# VideoFiltering.net
KiCad netlist of a schematic drawn in Altium Designer
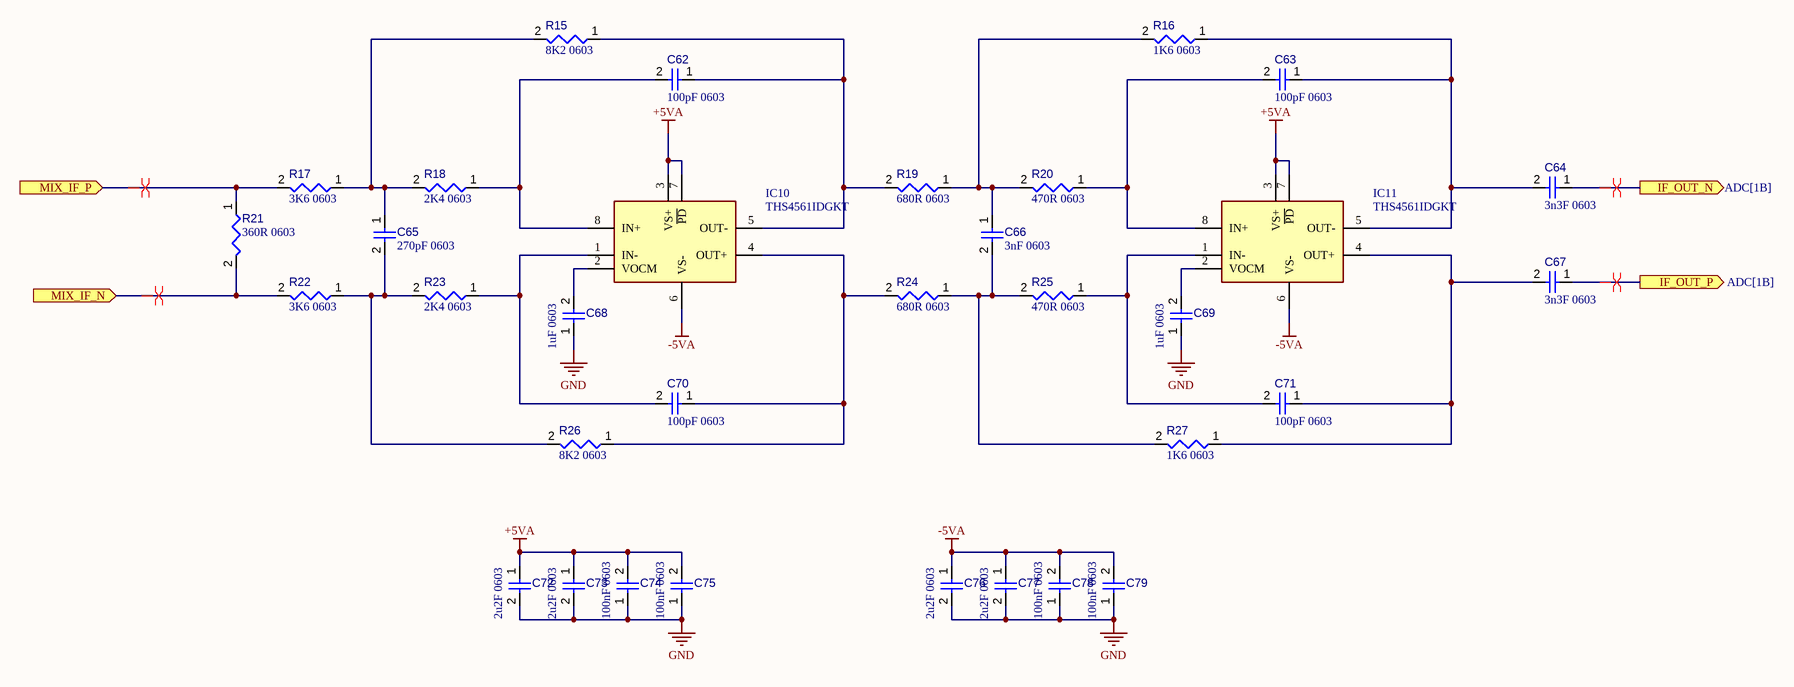
[diagram p0: VideoFiltering.SchDoc]

(export (version "E")
  (design (tool "Eeschema 10.0.6"))
  (components
    (comp (ref "C62")
      (value "100pF 0603")
      (footprint "CAPC0603(1608)100_L")
      (description "Chip Capacitor, 1µF +/-0.1%, 25V, 0603, Thickness 1 mm")
      (fields (field (name "TOLERANCE") "20%") (field (name "MANUFACTURER PART NO") "06033A101GAT2A"))
      (libsource (lib "Kavija Karunarathna") (part "CAP-NP-2"))
    )
    (comp (ref "C63")
      (value "100pF 0603")
      (footprint "CAPC0603(1608)100_L")
      (description "Chip Capacitor, 1µF +/-0.1%, 25V, 0603, Thickness 1 mm")
      (fields (field (name "TOLERANCE") "20%") (field (name "MANUFACTURER PART NO") "06033A101GAT2A"))
      (libsource (lib "Kavija Karunarathna") (part "CAP-NP-2"))
    )
    (comp (ref "C64")
      (value "3n3F 0603")
      (footprint "CAPC0603(1608)100_L")
      (description "Chip Capacitor, 1µF +/-0.1%, 25V, 0603, Thickness 1 mm")
      (fields (field (name "TOLERANCE") "20%") (field (name "MANUFACTURER PART NO") "VJ0603Y332JXBAC"))
      (libsource (lib "Kavija Karunarathna") (part "CAP-NP-2"))
    )
    (comp (ref "C65")
      (value "270pF 0603")
      (footprint "CAPC0603(1608)100_L")
      (description "Chip Capacitor, 1µF +/-0.1%, 25V, 0603, Thickness 1 mm")
      (fields (field (name "TOLERANCE") "20%") (field (name "MANUFACTURER PART NO") "C0603C271J1GACAUTO"))
      (libsource (lib "Kavija Karunarathna") (part "CAP-NP-2"))
    )
    (comp (ref "C66")
      (value "3nF 0603")
      (footprint "CAPC0603(1608)100_L")
      (description "Chip Capacitor, 1µF +/-0.1%, 25V, 0603, Thickness 1 mm")
      (fields (field (name "TOLERANCE") "20%") (field (name "MANUFACTURER PART NO") "C0603C302K5GACTU"))
      (libsource (lib "Kavija Karunarathna") (part "CAP-NP-2"))
    )
    (comp (ref "C67")
      (value "3n3F 0603")
      (footprint "CAPC0603(1608)100_L")
      (description "Chip Capacitor, 1µF +/-0.1%, 25V, 0603, Thickness 1 mm")
      (fields (field (name "TOLERANCE") "20%") (field (name "MANUFACTURER PART NO") "VJ0603Y332JXBAC"))
      (libsource (lib "Kavija Karunarathna") (part "CAP-NP-2"))
    )
    (comp (ref "C68")
      (value "1uF 0603")
      (footprint "CAPC0603(1608)100_L")
      (description "Chip Capacitor, 1µF +/-0.1%, 25V, 0603, Thickness 1 mm")
      (fields (field (name "TOLERANCE") "20%") (field (name "MANUFACTURER PART NO") "0603YC105KAZ2A"))
      (libsource (lib "Kavija Karunarathna") (part "CAP-NP-2"))
    )
    (comp (ref "C69")
      (value "1uF 0603")
      (footprint "CAPC0603(1608)100_L")
      (description "Chip Capacitor, 1µF +/-0.1%, 25V, 0603, Thickness 1 mm")
      (fields (field (name "TOLERANCE") "20%") (field (name "MANUFACTURER PART NO") "0603YC105KAZ2A"))
      (libsource (lib "Kavija Karunarathna") (part "CAP-NP-2"))
    )
    (comp (ref "C70")
      (value "100pF 0603")
      (footprint "CAPC0603(1608)100_L")
      (description "Chip Capacitor, 1µF +/-0.1%, 25V, 0603, Thickness 1 mm")
      (fields (field (name "TOLERANCE") "20%") (field (name "MANUFACTURER PART NO") "06033A101GAT2A"))
      (libsource (lib "Kavija Karunarathna") (part "CAP-NP-2"))
    )
    (comp (ref "C71")
      (value "100pF 0603")
      (footprint "CAPC0603(1608)100_L")
      (description "Chip Capacitor, 1µF +/-0.1%, 25V, 0603, Thickness 1 mm")
      (fields (field (name "TOLERANCE") "20%") (field (name "MANUFACTURER PART NO") "06033A101GAT2A"))
      (libsource (lib "Kavija Karunarathna") (part "CAP-NP-2"))
    )
    (comp (ref "C72")
      (value "2u2F 0603")
      (footprint "CAPC0603(1608)100_L")
      (description "Multilayer Ceramic Capacitors MLCC - SMD/SMT 0603 10nF 16volts X7R 10%")
      (fields (field (name "TOLERANCE") "20%") (field (name "MANUFACTURER PART NO") "VJ0603G225KXQCW1BC"))
      (libsource (lib "Kavija Karunarathna") (part "CAP-NP-2"))
    )
    (comp (ref "C73")
      (value "2u2F 0603")
      (footprint "CAPC0603(1608)100_L")
      (description "Multilayer Ceramic Capacitors MLCC - SMD/SMT 0603 10nF 16volts X7R 10%")
      (fields (field (name "TOLERANCE") "20%") (field (name "MANUFACTURER PART NO") "VJ0603G225KXQCW1BC"))
      (libsource (lib "Kavija Karunarathna") (part "CAP-NP-2"))
    )
    (comp (ref "C74")
      (value "100nF 0603")
      (footprint "CAPC0603(1608)100_L")
      (description "Chip Capacitor, 1µF +/-0.1%, 25V, 0603, Thickness 1 mm")
      (fields (field (name "TOLERANCE") "20%") (field (name "MANUFACTURER PART NO") "0603X104K250CT"))
      (libsource (lib "Kavija Karunarathna") (part "CAP-NP-2"))
    )
    (comp (ref "C75")
      (value "100nF 0603")
      (footprint "CAPC0603(1608)100_L")
      (description "Chip Capacitor, 1µF +/-0.1%, 25V, 0603, Thickness 1 mm")
      (fields (field (name "TOLERANCE") "20%") (field (name "MANUFACTURER PART NO") "0603X104K250CT"))
      (libsource (lib "Kavija Karunarathna") (part "CAP-NP-2"))
    )
    (comp (ref "C76")
      (value "2u2F 0603")
      (footprint "CAPC0603(1608)100_L")
      (description "Multilayer Ceramic Capacitors MLCC - SMD/SMT 0603 10nF 16volts X7R 10%")
      (fields (field (name "TOLERANCE") "20%") (field (name "MANUFACTURER PART NO") "VJ0603G225KXQCW1BC"))
      (libsource (lib "Kavija Karunarathna") (part "CAP-NP-2"))
    )
    (comp (ref "C77")
      (value "2u2F 0603")
      (footprint "CAPC0603(1608)100_L")
      (description "Multilayer Ceramic Capacitors MLCC - SMD/SMT 0603 10nF 16volts X7R 10%")
      (fields (field (name "TOLERANCE") "20%") (field (name "MANUFACTURER PART NO") "VJ0603G225KXQCW1BC"))
      (libsource (lib "Kavija Karunarathna") (part "CAP-NP-2"))
    )
    (comp (ref "C78")
      (value "100nF 0603")
      (footprint "CAPC0603(1608)100_L")
      (description "Chip Capacitor, 1µF +/-0.1%, 25V, 0603, Thickness 1 mm")
      (fields (field (name "TOLERANCE") "20%") (field (name "MANUFACTURER PART NO") "0603X104K250CT"))
      (libsource (lib "Kavija Karunarathna") (part "CAP-NP-2"))
    )
    (comp (ref "C79")
      (value "100nF 0603")
      (footprint "CAPC0603(1608)100_L")
      (description "Chip Capacitor, 1µF +/-0.1%, 25V, 0603, Thickness 1 mm")
      (fields (field (name "TOLERANCE") "20%") (field (name "MANUFACTURER PART NO") "0603X104K250CT"))
      (libsource (lib "Kavija Karunarathna") (part "CAP-NP-2"))
    )
    (comp (ref "IC10")
      (value "THS4561IDGKT")
      (footprint "SOP65P490X110-8N")
      (description "Integrated Circuit")
      (fields (field (name "MOUSER PART NO") "595-THS4561IDGKT"))
      (libsource (lib "SchLib") (part "THS4561IDGKT"))
    )
    (comp (ref "IC11")
      (value "THS4561IDGKT")
      (footprint "SOP65P490X110-8N")
      (description "Integrated Circuit")
      (fields (field (name "MOUSER PART NO") "595-THS4561IDGKT"))
      (libsource (lib "SchLib") (part "THS4561IDGKT"))
    )
    (comp (ref "R15")
      (value "8K2 0603")
      (footprint "RESC0603(1608)_L")
      (description "Thick Film Resistors - SMD WRIS-RSKS 100 Ohms 1 % 0.1 W 0603 AEC-Q200")
      (fields (field (name "POWER") "100mW") (field (name "TOLERANCE") "5%"))
      (libsource (lib "Kavija Karunarathna") (part "120R3J"))
    )
    (comp (ref "R16")
      (value "1K6 0603")
      (footprint "RESC0603(1608)_L")
      (description "Thick Film Resistors - SMD WRIS-RSKS 100 Ohms 1 % 0.1 W 0603 AEC-Q200")
      (fields (field (name "POWER") "100mW") (field (name "TOLERANCE") "5%"))
      (libsource (lib "Kavija Karunarathna") (part "120R3J"))
    )
    (comp (ref "R17")
      (value "3K6 0603")
      (footprint "RESC0603(1608)_L")
      (description "Thick Film Resistors - SMD WRIS-RSKS 100 Ohms 1 % 0.1 W 0603 AEC-Q200")
      (fields (field (name "POWER") "100mW") (field (name "TOLERANCE") "5%"))
      (libsource (lib "Kavija Karunarathna") (part "120R3J"))
    )
    (comp (ref "R18")
      (value "2K4 0603")
      (footprint "RESC0603(1608)_L")
      (description "Thick Film Resistors - SMD WRIS-RSKS 100 Ohms 1 % 0.1 W 0603 AEC-Q200")
      (fields (field (name "POWER") "100mW") (field (name "TOLERANCE") "5%"))
      (libsource (lib "Kavija Karunarathna") (part "120R3J"))
    )
    (comp (ref "R19")
      (value "680R 0603")
      (footprint "RESC0603(1608)_L")
      (description "Thick Film Resistors - SMD WRIS-RSKS 100 Ohms 1 % 0.1 W 0603 AEC-Q200")
      (fields (field (name "POWER") "100mW") (field (name "TOLERANCE") "5%"))
      (libsource (lib "Kavija Karunarathna") (part "120R3J"))
    )
    (comp (ref "R20")
      (value "470R 0603")
      (footprint "RESC0603(1608)_L")
      (description "Thick Film Resistors - SMD WRIS-RSKS 100 Ohms 1 % 0.1 W 0603 AEC-Q200")
      (fields (field (name "POWER") "100mW") (field (name "TOLERANCE") "5%"))
      (libsource (lib "Kavija Karunarathna") (part "120R3J"))
    )
    (comp (ref "R21")
      (value "360R 0603")
      (footprint "RESC0603(1608)_L")
      (description "Thick Film Resistors - SMD WRIS-RSKS 100 Ohms 1 % 0.1 W 0603 AEC-Q200")
      (fields (field (name "POWER") "100mW") (field (name "TOLERANCE") "5%"))
      (libsource (lib "Kavija Karunarathna") (part "120R3J"))
    )
    (comp (ref "R22")
      (value "3K6 0603")
      (footprint "RESC0603(1608)_L")
      (description "Thick Film Resistors - SMD WRIS-RSKS 100 Ohms 1 % 0.1 W 0603 AEC-Q200")
      (fields (field (name "POWER") "100mW") (field (name "TOLERANCE") "5%"))
      (libsource (lib "Kavija Karunarathna") (part "120R3J"))
    )
    (comp (ref "R23")
      (value "2K4 0603")
      (footprint "RESC0603(1608)_L")
      (description "Thick Film Resistors - SMD WRIS-RSKS 100 Ohms 1 % 0.1 W 0603 AEC-Q200")
      (fields (field (name "POWER") "100mW") (field (name "TOLERANCE") "5%"))
      (libsource (lib "Kavija Karunarathna") (part "120R3J"))
    )
    (comp (ref "R24")
      (value "680R 0603")
      (footprint "RESC0603(1608)_L")
      (description "Thick Film Resistors - SMD WRIS-RSKS 100 Ohms 1 % 0.1 W 0603 AEC-Q200")
      (fields (field (name "POWER") "100mW") (field (name "TOLERANCE") "5%"))
      (libsource (lib "Kavija Karunarathna") (part "120R3J"))
    )
    (comp (ref "R25")
      (value "470R 0603")
      (footprint "RESC0603(1608)_L")
      (description "Thick Film Resistors - SMD WRIS-RSKS 100 Ohms 1 % 0.1 W 0603 AEC-Q200")
      (fields (field (name "POWER") "100mW") (field (name "TOLERANCE") "5%"))
      (libsource (lib "Kavija Karunarathna") (part "120R3J"))
    )
    (comp (ref "R26")
      (value "8K2 0603")
      (footprint "RESC0603(1608)_L")
      (description "Thick Film Resistors - SMD WRIS-RSKS 100 Ohms 1 % 0.1 W 0603 AEC-Q200")
      (fields (field (name "POWER") "100mW") (field (name "TOLERANCE") "5%"))
      (libsource (lib "Kavija Karunarathna") (part "120R3J"))
    )
    (comp (ref "R27")
      (value "1K6 0603")
      (footprint "RESC0603(1608)_L")
      (description "Thick Film Resistors - SMD WRIS-RSKS 100 Ohms 1 % 0.1 W 0603 AEC-Q200")
      (fields (field (name "POWER") "100mW") (field (name "TOLERANCE") "5%"))
      (libsource (lib "Kavija Karunarathna") (part "120R3J"))
    )
  )
  (nets
    (net (code "1") (name "+5VA") (class "Default")
      (node (ref "C72") (pin "1") (pinfunction "1_1") (pintype "passive"))
      (node (ref "C73") (pin "1") (pinfunction "1_1") (pintype "passive"))
      (node (ref "C74") (pin "2") (pinfunction "2_2") (pintype "passive"))
      (node (ref "C75") (pin "2") (pinfunction "2_2") (pintype "passive"))
      (node (ref "IC10") (pin "3") (pinfunction "VS+_3") (pintype "passive"))
      (node (ref "IC10") (pin "7") (pinfunction "~{PD}_7") (pintype "passive"))
      (node (ref "IC11") (pin "3") (pinfunction "VS+_3") (pintype "passive"))
      (node (ref "IC11") (pin "7") (pinfunction "~{PD}_7") (pintype "passive"))
    )
    (net (code "2") (name "-5VA") (class "Default")
      (node (ref "C76") (pin "1") (pinfunction "1_1") (pintype "passive"))
      (node (ref "C77") (pin "1") (pinfunction "1_1") (pintype "passive"))
      (node (ref "C78") (pin "2") (pinfunction "2_2") (pintype "passive"))
      (node (ref "C79") (pin "2") (pinfunction "2_2") (pintype "passive"))
      (node (ref "IC10") (pin "6") (pinfunction "VS-_6") (pintype "passive"))
      (node (ref "IC11") (pin "6") (pinfunction "VS-_6") (pintype "passive"))
    )
    (net (code "3") (name "/IF_OUT_N") (class "Default")
      (node (ref "C64") (pin "1") (pinfunction "1_1") (pintype "passive"))
    )
    (net (code "4") (name "/IF_OUT_P") (class "Default")
      (node (ref "C67") (pin "1") (pinfunction "1_1") (pintype "passive"))
    )
    (net (code "5") (name "/MIX_IF_N") (class "Default")
      (node (ref "R21") (pin "2") (pinfunction "2_2") (pintype "passive"))
      (node (ref "R22") (pin "2") (pinfunction "2_2") (pintype "passive"))
    )
    (net (code "6") (name "/MIX_IF_P") (class "Default")
      (node (ref "R17") (pin "2") (pinfunction "2_2") (pintype "passive"))
      (node (ref "R21") (pin "1") (pinfunction "1_1") (pintype "passive"))
    )
    (net (code "7") (name "GND") (class "Default")
      (node (ref "C68") (pin "1") (pinfunction "1_1") (pintype "passive"))
      (node (ref "C69") (pin "1") (pinfunction "1_1") (pintype "passive"))
      (node (ref "C72") (pin "2") (pinfunction "2_2") (pintype "passive"))
      (node (ref "C73") (pin "2") (pinfunction "2_2") (pintype "passive"))
      (node (ref "C74") (pin "1") (pinfunction "1_1") (pintype "passive"))
      (node (ref "C75") (pin "1") (pinfunction "1_1") (pintype "passive"))
      (node (ref "C76") (pin "2") (pinfunction "2_2") (pintype "passive"))
      (node (ref "C77") (pin "2") (pinfunction "2_2") (pintype "passive"))
      (node (ref "C78") (pin "1") (pinfunction "1_1") (pintype "passive"))
      (node (ref "C79") (pin "1") (pinfunction "1_1") (pintype "passive"))
    )
    (net (code "8") (name "Net-(C65-Pad1)") (class "Default")
      (node (ref "C65") (pin "1") (pinfunction "1_1") (pintype "passive"))
      (node (ref "R15") (pin "2") (pinfunction "2_2") (pintype "passive"))
      (node (ref "R17") (pin "1") (pinfunction "1_1") (pintype "passive"))
      (node (ref "R18") (pin "2") (pinfunction "2_2") (pintype "passive"))
    )
    (net (code "9") (name "Net-(C65-Pad2)") (class "Default")
      (node (ref "C65") (pin "2") (pinfunction "2_2") (pintype "passive"))
      (node (ref "R22") (pin "1") (pinfunction "1_1") (pintype "passive"))
      (node (ref "R23") (pin "2") (pinfunction "2_2") (pintype "passive"))
      (node (ref "R26") (pin "2") (pinfunction "2_2") (pintype "passive"))
    )
    (net (code "10") (name "Net-(C66-Pad1)") (class "Default")
      (node (ref "C66") (pin "1") (pinfunction "1_1") (pintype "passive"))
      (node (ref "R16") (pin "2") (pinfunction "2_2") (pintype "passive"))
      (node (ref "R19") (pin "1") (pinfunction "1_1") (pintype "passive"))
      (node (ref "R20") (pin "2") (pinfunction "2_2") (pintype "passive"))
    )
    (net (code "11") (name "Net-(C66-Pad2)") (class "Default")
      (node (ref "C66") (pin "2") (pinfunction "2_2") (pintype "passive"))
      (node (ref "R24") (pin "1") (pinfunction "1_1") (pintype "passive"))
      (node (ref "R25") (pin "2") (pinfunction "2_2") (pintype "passive"))
      (node (ref "R27") (pin "2") (pinfunction "2_2") (pintype "passive"))
    )
    (net (code "12") (name "Net-(IC10-IN+)") (class "Default")
      (node (ref "C62") (pin "2") (pinfunction "2_2") (pintype "passive"))
      (node (ref "IC10") (pin "8") (pinfunction "IN+_8") (pintype "passive"))
      (node (ref "R18") (pin "1") (pinfunction "1_1") (pintype "passive"))
    )
    (net (code "13") (name "Net-(IC10-IN-)") (class "Default")
      (node (ref "C70") (pin "2") (pinfunction "2_2") (pintype "passive"))
      (node (ref "IC10") (pin "1") (pinfunction "IN-_1") (pintype "passive"))
      (node (ref "R23") (pin "1") (pinfunction "1_1") (pintype "passive"))
    )
    (net (code "14") (name "Net-(IC10-OUT+)") (class "Default")
      (node (ref "C70") (pin "1") (pinfunction "1_1") (pintype "passive"))
      (node (ref "IC10") (pin "4") (pinfunction "OUT+_4") (pintype "passive"))
      (node (ref "R24") (pin "2") (pinfunction "2_2") (pintype "passive"))
      (node (ref "R26") (pin "1") (pinfunction "1_1") (pintype "passive"))
    )
    (net (code "15") (name "Net-(IC10-OUT-)") (class "Default")
      (node (ref "C62") (pin "1") (pinfunction "1_1") (pintype "passive"))
      (node (ref "IC10") (pin "5") (pinfunction "OUT-_5") (pintype "passive"))
      (node (ref "R15") (pin "1") (pinfunction "1_1") (pintype "passive"))
      (node (ref "R19") (pin "2") (pinfunction "2_2") (pintype "passive"))
    )
    (net (code "16") (name "Net-(IC10-VOCM)") (class "Default")
      (node (ref "C68") (pin "2") (pinfunction "2_2") (pintype "passive"))
      (node (ref "IC10") (pin "2") (pinfunction "VOCM_2") (pintype "passive"))
    )
    (net (code "17") (name "Net-(IC11-IN+)") (class "Default")
      (node (ref "C63") (pin "2") (pinfunction "2_2") (pintype "passive"))
      (node (ref "IC11") (pin "8") (pinfunction "IN+_8") (pintype "passive"))
      (node (ref "R20") (pin "1") (pinfunction "1_1") (pintype "passive"))
    )
    (net (code "18") (name "Net-(IC11-IN-)") (class "Default")
      (node (ref "C71") (pin "2") (pinfunction "2_2") (pintype "passive"))
      (node (ref "IC11") (pin "1") (pinfunction "IN-_1") (pintype "passive"))
      (node (ref "R25") (pin "1") (pinfunction "1_1") (pintype "passive"))
    )
    (net (code "19") (name "Net-(IC11-OUT+)") (class "Default")
      (node (ref "C67") (pin "2") (pinfunction "2_2") (pintype "passive"))
      (node (ref "C71") (pin "1") (pinfunction "1_1") (pintype "passive"))
      (node (ref "IC11") (pin "4") (pinfunction "OUT+_4") (pintype "passive"))
      (node (ref "R27") (pin "1") (pinfunction "1_1") (pintype "passive"))
    )
    (net (code "20") (name "Net-(IC11-OUT-)") (class "Default")
      (node (ref "C63") (pin "1") (pinfunction "1_1") (pintype "passive"))
      (node (ref "C64") (pin "2") (pinfunction "2_2") (pintype "passive"))
      (node (ref "IC11") (pin "5") (pinfunction "OUT-_5") (pintype "passive"))
      (node (ref "R16") (pin "1") (pinfunction "1_1") (pintype "passive"))
    )
    (net (code "21") (name "Net-(IC11-VOCM)") (class "Default")
      (node (ref "C69") (pin "2") (pinfunction "2_2") (pintype "passive"))
      (node (ref "IC11") (pin "2") (pinfunction "VOCM_2") (pintype "passive"))
    )
  )
)
